# AIR_Control1_Main_080116.net
KiCad netlist of a schematic drawn in Altium Designer
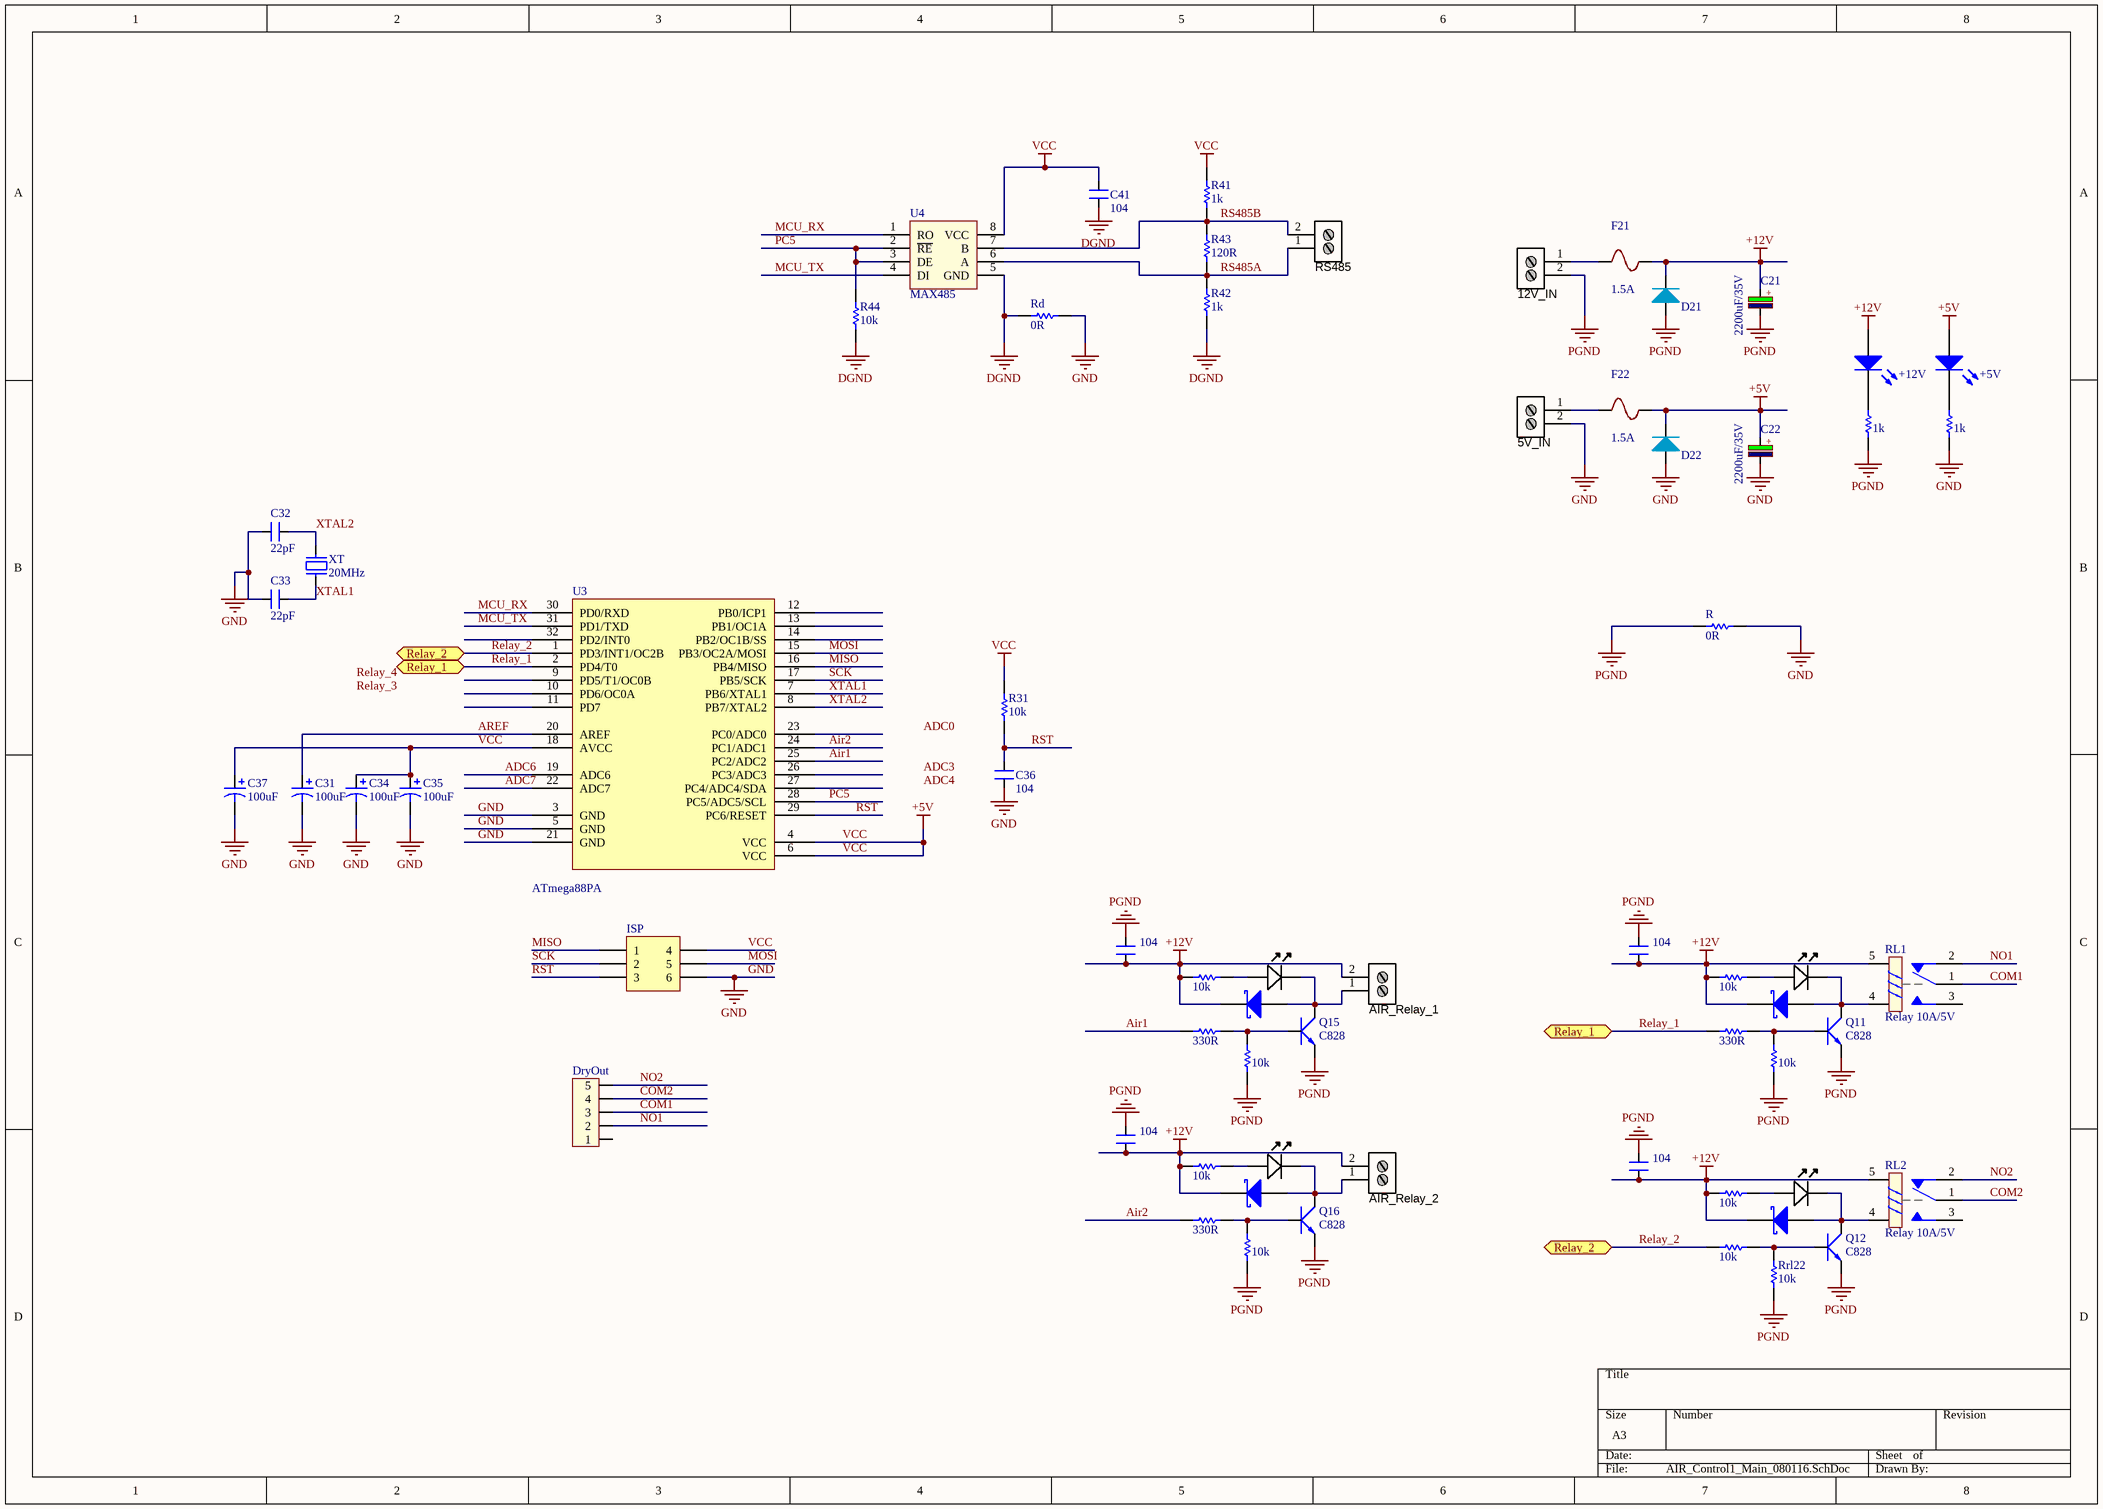
[diagram p0: AIR_Control1_Main_080116.SchDoc]

(export (version "E")
  (design (tool "Eeschema 10.0.6"))
  (components
    (comp (ref "+5V") (value "Led") (footprint "LED 5mm RED") (libsource (lib "Tuan") (part "Led")))
    (comp (ref "+12V") (value "Led") (footprint "LED 5mm RED") (libsource (lib "Tuan") (part "Led")))
    (comp (ref "5V_IN")
      (value "Stackable ScrewTerm")
      (footprint "2P_PCB_ScrewTerm_200mil")
      (description "Terminal Block Screw Type THT 2-Position 3.81mm pitch")
      (libsource (lib "") (part "2P_ScrewTerm_90S_3.81MM_1"))
    )
    (comp (ref "12V_IN")
      (value "Stackable ScrewTerm")
      (footprint "2P_PCB_ScrewTerm_200mil")
      (description "Terminal Block Screw Type THT 2-Position 3.81mm pitch")
      (libsource (lib "") (part "2P_ScrewTerm_90S_3.81MM_1"))
    )
    (comp (ref "AIR_Relay_1")
      (value "Stackable ScrewTerm")
      (footprint "2P_PCB_ScrewTerm_200mil")
      (description "Terminal Block Screw Type THT 2-Position 3.81mm pitch")
      (libsource (lib "PBL - Connectors") (part "2P_ScrewTerm_90S_3.81MM"))
    )
    (comp (ref "AIR_Relay_2")
      (value "Stackable ScrewTerm")
      (footprint "2P_PCB_ScrewTerm_200mil")
      (description "Terminal Block Screw Type THT 2-Position 3.81mm pitch")
      (libsource (lib "PBL - Connectors") (part "2P_ScrewTerm_90S_3.81MM"))
    )
    (comp (ref "C21")
      (value "2200uF/35V")
      (footprint "heromap:CP_1000uF_25V")
      (description "Cap 1000uF/16V - 220uF/50V")
      (libsource (lib "heromap") (part "CP4"))
    )
    (comp (ref "C22")
      (value "2200uF/35V")
      (footprint "heromap:CP_1000uF_25V")
      (description "Cap 1000uF/16V - 220uF/50V")
      (libsource (lib "heromap") (part "CP4"))
    )
    (comp (ref "C31")
      (value "100uF")
      (footprint "CAPC2012N_F")
      (fields (field (name "Comment") "Cap"))
      (libsource (lib "Tuan") (part "Cap"))
    )
    (comp (ref "C32")
      (value "22pF")
      (footprint "CAPC1608N")
      (fields (field (name "Comment") "CAP NP"))
      (libsource (lib "Tuan") (part "CAP NP"))
    )
    (comp (ref "C33")
      (value "22pF")
      (footprint "CAPC1608N")
      (fields (field (name "Comment") "CAP NP"))
      (libsource (lib "Tuan") (part "CAP NP"))
    )
    (comp (ref "C34")
      (value "100uF")
      (footprint "CAPC2012N_F")
      (fields (field (name "Comment") "Cap"))
      (libsource (lib "Tuan") (part "Cap"))
    )
    (comp (ref "C35")
      (value "100uF")
      (footprint "CAPC2012N_F")
      (fields (field (name "Comment") "Cap"))
      (libsource (lib "Tuan") (part "Cap"))
    )
    (comp (ref "C36")
      (value "104")
      (footprint "CAPC1608N")
      (fields (field (name "Comment") "CAP NP"))
      (libsource (lib "Tuan") (part "CAP NP"))
    )
    (comp (ref "C37")
      (value "100uF")
      (footprint "CAPC2012N_F")
      (fields (field (name "Comment") "Cap"))
      (libsource (lib "Tuan") (part "Cap"))
    )
    (comp (ref "C41")
      (value "104")
      (footprint "CAPC2012N_F")
      (fields (field (name "Comment") "100nF/104"))
      (libsource (lib "Tuan") (part "CAP NP"))
    )
    (comp (ref "Crl1")
      (value "104")
      (footprint "CAPC2012N_F")
      (fields (field (name "Comment") "CAP NP"))
      (libsource (lib "Tuan") (part "CAP NP"))
    )
    (comp (ref "Crl2")
      (value "104")
      (footprint "CAPC2012N_F")
      (fields (field (name "Comment") "CAP NP"))
      (libsource (lib "Tuan") (part "CAP NP"))
    )
    (comp (ref "Crl5")
      (value "104")
      (footprint "CAPC2012N_F")
      (fields (field (name "Comment") "CAP NP"))
      (libsource (lib "Tuan") (part "CAP NP"))
    )
    (comp (ref "Crl6")
      (value "104")
      (footprint "CAPC2012N_F")
      (fields (field (name "Comment") "CAP NP"))
      (libsource (lib "Tuan") (part "CAP NP"))
    )
    (comp (ref "D11") (value "Diode") (footprint "DO-214AC") (libsource (lib "") (part "Diode_1")))
    (comp (ref "D12") (value "Diode") (footprint "DO-214AC") (libsource (lib "") (part "Diode_1")))
    (comp (ref "D15") (value "Diode") (footprint "DO-214AC") (libsource (lib "") (part "Diode_1")))
    (comp (ref "D16") (value "Diode") (footprint "DO-214AC") (libsource (lib "") (part "Diode_1")))
    (comp (ref "D21") (value "Diode") (footprint "DO-214AC") (libsource (lib "Tuan") (part "Diode")))
    (comp (ref "D22") (value "Diode") (footprint "DO-214AC") (libsource (lib "Tuan") (part "Diode")))
    (comp (ref "DryOut")
      (value "JP5")
      (footprint "heromap:CON5")
      (description "Connector 5")
      (libsource (lib "heromap") (part "Con5"))
    )
    (comp (ref "E1")
      (value "Blue")
      (footprint "LED-0805-A")
      (description "LED 0805 SMD Blue 100mcd 470nm")
      (libsource (lib "PBL - Light Sources") (part "LED_SMD_Blue_0805_100mcd"))
    )
    (comp (ref "E2")
      (value "Blue")
      (footprint "LED-0805-A")
      (description "LED 0805 SMD Blue 100mcd 470nm")
      (libsource (lib "PBL - Light Sources") (part "LED_SMD_Blue_0805_100mcd"))
    )
    (comp (ref "E5")
      (value "Blue")
      (footprint "LED-0805-A")
      (description "LED 0805 SMD Blue 100mcd 470nm")
      (libsource (lib "PBL - Light Sources") (part "LED_SMD_Blue_0805_100mcd"))
    )
    (comp (ref "E6")
      (value "Blue")
      (footprint "LED-0805-A")
      (description "LED 0805 SMD Blue 100mcd 470nm")
      (libsource (lib "PBL - Light Sources") (part "LED_SMD_Blue_0805_100mcd"))
    )
    (comp (ref "F21") (value "1.5A") (footprint "FUSE_SR-5-BK") (libsource (lib "Tuan") (part "Fuse")))
    (comp (ref "F22") (value "1.5A") (footprint "FUSE_SR-5-BK") (libsource (lib "Tuan") (part "Fuse")))
    (comp (ref "ISP")
      (value "Header 3X2A")
      (footprint "HDR2X3_CEN")
      (description "Header, 3-Pin, Dual row")
      (fields (field (name "PUBLISHER") "Altium Limited"))
      (libsource (lib "Miscellaneous Connectors") (part "Header 3X2A"))
    )
    (comp (ref "Q11")
      (value "C828")
      (footprint "SOT23 TOP")
      (description "Transistor C828 C1815....")
      (libsource (lib "Tuan") (part "NPN"))
    )
    (comp (ref "Q12")
      (value "C828")
      (footprint "SOT23 TOP")
      (description "Transistor C828 C1815....")
      (libsource (lib "Tuan") (part "NPN"))
    )
    (comp (ref "Q15")
      (value "C828")
      (footprint "SOT23 TOP")
      (description "Transistor C828 C1815....")
      (libsource (lib "Tuan") (part "NPN"))
    )
    (comp (ref "Q16")
      (value "C828")
      (footprint "SOT23 TOP")
      (description "Transistor C828 C1815....")
      (libsource (lib "Tuan") (part "NPN"))
    )
    (comp (ref "R")
      (value "0R")
      (footprint "RESTH_AXIAL-0.4")
      (fields (field (name "Comment") "Res"))
      (libsource (lib "Tuan") (part "Res"))
    )
    (comp (ref "R21")
      (value "1k")
      (footprint "RESC2012N_F")
      (fields (field (name "Comment") "Res_0805_1k"))
      (libsource (lib "Tuan") (part "Res"))
    )
    (comp (ref "R22")
      (value "1k")
      (footprint "RESC2012N_F")
      (fields (field (name "Comment") "Res_0805_1k"))
      (libsource (lib "Tuan") (part "Res"))
    )
    (comp (ref "R31")
      (value "10k")
      (footprint "RESC1608N_ZERO")
      (fields (field (name "Comment") "Res"))
      (libsource (lib "Tuan") (part "Res"))
    )
    (comp (ref "R41")
      (value "1k")
      (footprint "RESC2012N_F")
      (description "Tro dan")
      (libsource (lib "GPS_Clock_v12") (part "Res"))
    )
    (comp (ref "R42")
      (value "1k")
      (footprint "RESC2012N_F")
      (description "Tro dan")
      (libsource (lib "GPS_Clock_v12") (part "Res"))
    )
    (comp (ref "R43")
      (value "120R")
      (footprint "RESC2012N_F")
      (description "Tro dan")
      (fields (field (name "Comment") "330R"))
      (libsource (lib "GPS_Clock_v12") (part "Res"))
    )
    (comp (ref "R44")
      (value "10k")
      (footprint "RESC2012N_F")
      (description "Tro dan")
      (fields (field (name "Comment") "330R"))
      (libsource (lib "GPS_Clock_v12") (part "Res"))
    )
    (comp (ref "Rd")
      (value "0R")
      (footprint "RESC2012N_F")
      (fields (field (name "Comment") "Res"))
      (libsource (lib "Tuan") (part "Res"))
    )
    (comp (ref "RL1")
      (value "Relay 10A/5V")
      (footprint "RL_5PIN")
      (description "Relay SPDT,10A - 12VDC 5 Pin")
      (libsource (lib "syhaunguyen") (part "Relay 1"))
    )
    (comp (ref "RL2")
      (value "Relay 10A/5V")
      (footprint "RL_5PIN")
      (description "Relay SPDT,10A - 12VDC 5 Pin")
      (libsource (lib "syhaunguyen") (part "Relay 1"))
    )
    (comp (ref "Rl52")
      (value "10k")
      (footprint "RESC1608N_ZERO")
      (fields (field (name "Comment") "Res"))
      (libsource (lib "Tuan") (part "Res"))
    )
    (comp (ref "Rrl11")
      (value "330R")
      (footprint "RESC1608N_ZERO")
      (fields (field (name "Comment") "Res"))
      (libsource (lib "Tuan") (part "Res"))
    )
    (comp (ref "Rrl12")
      (value "10k")
      (footprint "RESC1608N_ZERO")
      (fields (field (name "Comment") "Res"))
      (libsource (lib "Tuan") (part "Res"))
    )
    (comp (ref "Rrl13")
      (value "10k")
      (footprint "RESC1608N_ZERO")
      (fields (field (name "Comment") "Res"))
      (libsource (lib "Tuan") (part "Res"))
    )
    (comp (ref "Rrl21")
      (value "10k")
      (footprint "RESC1608N_ZERO")
      (fields (field (name "Comment") "Res"))
      (libsource (lib "Tuan") (part "Res"))
    )
    (comp (ref "Rrl22")
      (value "10k")
      (footprint "RESC1608N_ZERO")
      (fields (field (name "Comment") "Res"))
      (libsource (lib "Tuan") (part "Res"))
    )
    (comp (ref "Rrl23")
      (value "10k")
      (footprint "RESC1608N_ZERO")
      (fields (field (name "Comment") "Res"))
      (libsource (lib "Tuan") (part "Res"))
    )
    (comp (ref "Rrl51")
      (value "330R")
      (footprint "RESC1608N_ZERO")
      (fields (field (name "Comment") "Res"))
      (libsource (lib "Tuan") (part "Res"))
    )
    (comp (ref "Rrl53")
      (value "10k")
      (footprint "RESC1608N_ZERO")
      (fields (field (name "Comment") "Res"))
      (libsource (lib "Tuan") (part "Res"))
    )
    (comp (ref "Rrl61")
      (value "330R")
      (footprint "RESC1608N_ZERO")
      (fields (field (name "Comment") "Res"))
      (libsource (lib "Tuan") (part "Res"))
    )
    (comp (ref "Rrl62")
      (value "10k")
      (footprint "RESC1608N_ZERO")
      (fields (field (name "Comment") "Res"))
      (libsource (lib "Tuan") (part "Res"))
    )
    (comp (ref "Rrl63")
      (value "10k")
      (footprint "RESC1608N_ZERO")
      (fields (field (name "Comment") "Res"))
      (libsource (lib "Tuan") (part "Res"))
    )
    (comp (ref "RS485")
      (value "Stackable ScrewTerm")
      (footprint "2P_PCB1")
      (description "Terminal Block Screw Type THT 2-Position 3.81mm pitch")
      (libsource (lib "PBL - Connectors") (part "2P_ScrewTerm_90S_3.81MM"))
    )
    (comp (ref "U3")
      (value "ATmega88PA")
      (footprint "32PIN")
      (description "ATmega48/168/328")
      (libsource (lib "Tuan") (part "ATmega48/168/328"))
    )
    (comp (ref "U4")
      (value "MAX485")
      (footprint "SO-8")
      (description "RS232 - RS485 (Same sn75176)")
      (libsource (lib "heromap") (part "MAX485"))
    )
    (comp (ref "XT") (value "20MHz") (footprint "XT2") (libsource (lib "Tuan") (part "Crystal")))
  )
  (nets
    (net (code "1") (name "+5V") (class "Default")
      (node (ref "+5V") (pin "1") (pinfunction "A_1") (pintype "passive"))
      (node (ref "C22") (pin "1") (pinfunction "1_1") (pintype "passive"))
      (node (ref "C34") (pin "1") (pinfunction "1_1") (pintype "passive"))
      (node (ref "C35") (pin "1") (pinfunction "1_1") (pintype "passive"))
      (node (ref "C37") (pin "1") (pinfunction "1_1") (pintype "passive"))
      (node (ref "C41") (pin "2") (pinfunction "2_2") (pintype "passive"))
      (node (ref "D22") (pin "2") (pinfunction "K_2") (pintype "passive"))
      (node (ref "F22") (pin "2") (pinfunction "2_2") (pintype "passive"))
      (node (ref "ISP") (pin "4") (pinfunction "4_4") (pintype "passive"))
      (node (ref "R31") (pin "2") (pinfunction "2_2") (pintype "passive"))
      (node (ref "R41") (pin "2") (pinfunction "2_2") (pintype "passive"))
      (node (ref "U3") (pin "18") (pinfunction "AVCC_18") (pintype "passive"))
      (node (ref "U3") (pin "4") (pinfunction "VCC_4") (pintype "passive"))
      (node (ref "U3") (pin "6") (pinfunction "VCC_6") (pintype "passive"))
      (node (ref "U4") (pin "8") (pinfunction "VCC_8") (pintype "passive"))
    )
    (net (code "2") (name "+12V") (class "Default")
      (node (ref "+12V") (pin "1") (pinfunction "A_1") (pintype "passive"))
      (node (ref "AIR_Relay_1") (pin "2") (pinfunction "2_2") (pintype "passive"))
      (node (ref "AIR_Relay_2") (pin "2") (pinfunction "2_2") (pintype "passive"))
      (node (ref "C21") (pin "1") (pinfunction "1_1") (pintype "passive"))
      (node (ref "Crl1") (pin "1") (pinfunction "1_1") (pintype "passive"))
      (node (ref "Crl2") (pin "1") (pinfunction "1_1") (pintype "passive"))
      (node (ref "Crl5") (pin "1") (pinfunction "1_1") (pintype "passive"))
      (node (ref "Crl6") (pin "1") (pinfunction "1_1") (pintype "passive"))
      (node (ref "D11") (pin "2") (pinfunction "K_2") (pintype "passive"))
      (node (ref "D12") (pin "2") (pinfunction "K_2") (pintype "passive"))
      (node (ref "D15") (pin "2") (pinfunction "K_2") (pintype "passive"))
      (node (ref "D16") (pin "2") (pinfunction "K_2") (pintype "passive"))
      (node (ref "D21") (pin "2") (pinfunction "K_2") (pintype "passive"))
      (node (ref "F21") (pin "2") (pinfunction "2_2") (pintype "passive"))
      (node (ref "RL1") (pin "5") (pinfunction "5_5") (pintype "passive"))
      (node (ref "RL2") (pin "5") (pinfunction "5_5") (pintype "passive"))
      (node (ref "Rrl13") (pin "2") (pinfunction "2_2") (pintype "passive"))
      (node (ref "Rrl23") (pin "2") (pinfunction "2_2") (pintype "passive"))
      (node (ref "Rrl53") (pin "2") (pinfunction "2_2") (pintype "passive"))
      (node (ref "Rrl63") (pin "2") (pinfunction "2_2") (pintype "passive"))
    )
    (net (code "6") (name "/ADC6") (class "Default")
      (node (ref "U3") (pin "19") (pinfunction "ADC6_19") (pintype "passive"))
    )
    (net (code "7") (name "/ADC7") (class "Default")
      (node (ref "U3") (pin "22") (pinfunction "ADC7_22") (pintype "passive"))
    )
    (net (code "8") (name "/AREF") (class "Default")
      (node (ref "C31") (pin "1") (pinfunction "1_1") (pintype "passive"))
      (node (ref "U3") (pin "20") (pinfunction "AREF_20") (pintype "passive"))
    )
    (net (code "9") (name "/Air1") (class "Default")
      (node (ref "Rrl51") (pin "1") (pinfunction "1_1") (pintype "passive"))
      (node (ref "U3") (pin "25") (pinfunction "PC2/ADC2_25") (pintype "passive"))
    )
    (net (code "10") (name "/Air2") (class "Default")
      (node (ref "Rrl61") (pin "1") (pinfunction "1_1") (pintype "passive"))
      (node (ref "U3") (pin "24") (pinfunction "PC1/ADC1_24") (pintype "passive"))
    )
    (net (code "11") (name "/COM1") (class "Default")
      (node (ref "DryOut") (pin "3") (pinfunction "3_3") (pintype "passive"))
      (node (ref "RL1") (pin "1") (pinfunction "1_1") (pintype "passive"))
    )
    (net (code "12") (name "/COM2") (class "Default")
      (node (ref "DryOut") (pin "4") (pinfunction "4_4") (pintype "passive"))
      (node (ref "RL2") (pin "1") (pinfunction "1_1") (pintype "passive"))
    )
    (net (code "13") (name "/MCU_RX") (class "Default")
      (node (ref "U3") (pin "30") (pinfunction "PD0/RXD_30") (pintype "passive"))
      (node (ref "U4") (pin "1") (pinfunction "RO_1") (pintype "passive"))
    )
    (net (code "14") (name "/MCU_TX") (class "Default")
      (node (ref "U3") (pin "31") (pinfunction "PD1/TXD_31") (pintype "passive"))
      (node (ref "U4") (pin "4") (pinfunction "DI_4") (pintype "passive"))
    )
    (net (code "15") (name "/MISO") (class "Default")
      (node (ref "ISP") (pin "1") (pinfunction "1_1") (pintype "passive"))
      (node (ref "U3") (pin "16") (pinfunction "PB4/MISO_16") (pintype "passive"))
    )
    (net (code "16") (name "/MOSI") (class "Default")
      (node (ref "ISP") (pin "5") (pinfunction "5_5") (pintype "passive"))
      (node (ref "U3") (pin "15") (pinfunction "PB3/OC2A/MOSI_15") (pintype "passive"))
    )
    (net (code "17") (name "/NO1") (class "Default")
      (node (ref "DryOut") (pin "2") (pinfunction "2_2") (pintype "passive"))
      (node (ref "RL1") (pin "2") (pinfunction "2_2") (pintype "passive"))
    )
    (net (code "18") (name "/NO2") (class "Default")
      (node (ref "DryOut") (pin "5") (pinfunction "5_5") (pintype "passive"))
      (node (ref "RL2") (pin "2") (pinfunction "2_2") (pintype "passive"))
    )
    (net (code "19") (name "/PC5") (class "Default")
      (node (ref "R44") (pin "2") (pinfunction "2_2") (pintype "passive"))
      (node (ref "U3") (pin "28") (pinfunction "PC5/ADC5/SCL_28") (pintype "passive"))
      (node (ref "U4") (pin "2") (pinfunction "~{RE}_2") (pintype "passive"))
      (node (ref "U4") (pin "3") (pinfunction "DE_3") (pintype "passive"))
    )
    (net (code "20") (name "/RS485A") (class "Default")
      (node (ref "R42") (pin "2") (pinfunction "2_2") (pintype "passive"))
      (node (ref "R43") (pin "1") (pinfunction "1_1") (pintype "passive"))
      (node (ref "RS485") (pin "1") (pinfunction "1_1") (pintype "passive"))
      (node (ref "U4") (pin "6") (pinfunction "A_6") (pintype "passive"))
    )
    (net (code "21") (name "/RS485B") (class "Default")
      (node (ref "R41") (pin "1") (pinfunction "1_1") (pintype "passive"))
      (node (ref "R43") (pin "2") (pinfunction "2_2") (pintype "passive"))
      (node (ref "RS485") (pin "2") (pinfunction "2_2") (pintype "passive"))
      (node (ref "U4") (pin "7") (pinfunction "B_7") (pintype "passive"))
    )
    (net (code "22") (name "/RST") (class "Default")
      (node (ref "C36") (pin "2") (pinfunction "2_2") (pintype "passive"))
      (node (ref "ISP") (pin "3") (pinfunction "3_3") (pintype "passive"))
      (node (ref "R31") (pin "1") (pinfunction "1_1") (pintype "passive"))
      (node (ref "U3") (pin "29") (pinfunction "PC6/RESET_29") (pintype "passive"))
    )
    (net (code "23") (name "/Relay_1") (class "Default")
      (node (ref "Rrl11") (pin "1") (pinfunction "1_1") (pintype "passive"))
      (node (ref "U3") (pin "2") (pinfunction "PD4/T0_2") (pintype "passive"))
    )
    (net (code "24") (name "/Relay_2") (class "Default")
      (node (ref "Rrl21") (pin "1") (pinfunction "1_1") (pintype "passive"))
      (node (ref "U3") (pin "1") (pinfunction "PD3/INT1/OC2B_1") (pintype "passive"))
    )
    (net (code "27") (name "/SCK") (class "Default")
      (node (ref "ISP") (pin "2") (pinfunction "2_2") (pintype "passive"))
      (node (ref "U3") (pin "17") (pinfunction "PB5/SCK_17") (pintype "passive"))
    )
    (net (code "28") (name "/XTAL1") (class "Default")
      (node (ref "C33") (pin "1") (pinfunction "1_1") (pintype "passive"))
      (node (ref "U3") (pin "7") (pinfunction "PB6/XTAL1_7") (pintype "passive"))
      (node (ref "XT") (pin "1") (pinfunction "1_1") (pintype "passive"))
    )
    (net (code "29") (name "/XTAL2") (class "Default")
      (node (ref "C32") (pin "1") (pinfunction "1_1") (pintype "passive"))
      (node (ref "U3") (pin "8") (pinfunction "PB7/XTAL2_8") (pintype "passive"))
      (node (ref "XT") (pin "2") (pinfunction "2_2") (pintype "passive"))
    )
    (net (code "30") (name "DGND") (class "Default")
      (node (ref "C41") (pin "1") (pinfunction "1_1") (pintype "passive"))
      (node (ref "R42") (pin "1") (pinfunction "1_1") (pintype "passive"))
      (node (ref "R44") (pin "1") (pinfunction "1_1") (pintype "passive"))
      (node (ref "Rd") (pin "1") (pinfunction "1_1") (pintype "passive"))
      (node (ref "U4") (pin "5") (pinfunction "GND_5") (pintype "passive"))
    )
    (net (code "31") (name "GND") (class "Default")
      (node (ref "5V_IN") (pin "2") (pinfunction "2_2") (pintype "passive"))
      (node (ref "C22") (pin "2") (pinfunction "2_2") (pintype "passive"))
      (node (ref "C31") (pin "2") (pinfunction "2_2") (pintype "passive"))
      (node (ref "C32") (pin "2") (pinfunction "2_2") (pintype "passive"))
      (node (ref "C33") (pin "2") (pinfunction "2_2") (pintype "passive"))
      (node (ref "C34") (pin "2") (pinfunction "2_2") (pintype "passive"))
      (node (ref "C35") (pin "2") (pinfunction "2_2") (pintype "passive"))
      (node (ref "C36") (pin "1") (pinfunction "1_1") (pintype "passive"))
      (node (ref "C37") (pin "2") (pinfunction "2_2") (pintype "passive"))
      (node (ref "D22") (pin "1") (pinfunction "A_1") (pintype "passive"))
      (node (ref "ISP") (pin "6") (pinfunction "6_6") (pintype "passive"))
      (node (ref "R") (pin "2") (pinfunction "2_2") (pintype "passive"))
      (node (ref "R22") (pin "2") (pinfunction "2_2") (pintype "passive"))
      (node (ref "Rd") (pin "2") (pinfunction "2_2") (pintype "passive"))
      (node (ref "U3") (pin "21") (pinfunction "GND_21") (pintype "power_in"))
      (node (ref "U3") (pin "3") (pinfunction "GND_3") (pintype "power_in"))
      (node (ref "U3") (pin "5") (pinfunction "GND_5") (pintype "power_in"))
    )
    (net (code "32") (name "Net-(+5V-K)") (class "Default")
      (node (ref "+5V") (pin "2") (pinfunction "K_2") (pintype "passive"))
      (node (ref "R22") (pin "1") (pinfunction "1_1") (pintype "passive"))
    )
    (net (code "33") (name "Net-(+12V-K)") (class "Default")
      (node (ref "+12V") (pin "2") (pinfunction "K_2") (pintype "passive"))
      (node (ref "R21") (pin "1") (pinfunction "1_1") (pintype "passive"))
    )
    (net (code "34") (name "Net-(5V_IN-Pad1)") (class "Default")
      (node (ref "5V_IN") (pin "1") (pinfunction "1_1") (pintype "passive"))
      (node (ref "F22") (pin "1") (pinfunction "1_1") (pintype "passive"))
    )
    (net (code "35") (name "Net-(12V_IN-Pad1)") (class "Default")
      (node (ref "12V_IN") (pin "1") (pinfunction "1_1") (pintype "passive"))
      (node (ref "F21") (pin "1") (pinfunction "1_1") (pintype "passive"))
    )
    (net (code "36") (name "Net-(D11-A)") (class "Default")
      (node (ref "D11") (pin "1") (pinfunction "A_1") (pintype "passive"))
      (node (ref "E1") (pin "K") (pinfunction "K_K") (pintype "passive"))
      (node (ref "Q11") (pin "2") (pinfunction "C_2") (pintype "passive"))
      (node (ref "RL1") (pin "4") (pinfunction "4_4") (pintype "passive"))
    )
    (net (code "37") (name "Net-(D12-A)") (class "Default")
      (node (ref "D12") (pin "1") (pinfunction "A_1") (pintype "passive"))
      (node (ref "E2") (pin "K") (pinfunction "K_K") (pintype "passive"))
      (node (ref "Q12") (pin "2") (pinfunction "C_2") (pintype "passive"))
      (node (ref "RL2") (pin "4") (pinfunction "4_4") (pintype "passive"))
    )
    (net (code "38") (name "Net-(D15-A)") (class "Default")
      (node (ref "AIR_Relay_1") (pin "1") (pinfunction "1_1") (pintype "passive"))
      (node (ref "D15") (pin "1") (pinfunction "A_1") (pintype "passive"))
      (node (ref "E5") (pin "K") (pinfunction "K_K") (pintype "passive"))
      (node (ref "Q15") (pin "2") (pinfunction "C_2") (pintype "passive"))
    )
    (net (code "39") (name "Net-(D16-A)") (class "Default")
      (node (ref "AIR_Relay_2") (pin "1") (pinfunction "1_1") (pintype "passive"))
      (node (ref "D16") (pin "1") (pinfunction "A_1") (pintype "passive"))
      (node (ref "E6") (pin "K") (pinfunction "K_K") (pintype "passive"))
      (node (ref "Q16") (pin "2") (pinfunction "C_2") (pintype "passive"))
    )
    (net (code "40") (name "Net-(E1-PadA)") (class "Default")
      (node (ref "E1") (pin "A") (pinfunction "A_A") (pintype "passive"))
      (node (ref "Rrl13") (pin "1") (pinfunction "1_1") (pintype "passive"))
    )
    (net (code "41") (name "Net-(E2-PadA)") (class "Default")
      (node (ref "E2") (pin "A") (pinfunction "A_A") (pintype "passive"))
      (node (ref "Rrl23") (pin "1") (pinfunction "1_1") (pintype "passive"))
    )
    (net (code "42") (name "Net-(E5-PadA)") (class "Default")
      (node (ref "E5") (pin "A") (pinfunction "A_A") (pintype "passive"))
      (node (ref "Rrl53") (pin "1") (pinfunction "1_1") (pintype "passive"))
    )
    (net (code "43") (name "Net-(E6-PadA)") (class "Default")
      (node (ref "E6") (pin "A") (pinfunction "A_A") (pintype "passive"))
      (node (ref "Rrl63") (pin "1") (pinfunction "1_1") (pintype "passive"))
    )
    (net (code "44") (name "Net-(Q11-B)") (class "Default")
      (node (ref "Q11") (pin "1") (pinfunction "B_1") (pintype "passive"))
      (node (ref "Rrl11") (pin "2") (pinfunction "2_2") (pintype "passive"))
      (node (ref "Rrl12") (pin "2") (pinfunction "2_2") (pintype "passive"))
    )
    (net (code "45") (name "Net-(Q12-B)") (class "Default")
      (node (ref "Q12") (pin "1") (pinfunction "B_1") (pintype "passive"))
      (node (ref "Rrl21") (pin "2") (pinfunction "2_2") (pintype "passive"))
      (node (ref "Rrl22") (pin "2") (pinfunction "2_2") (pintype "passive"))
    )
    (net (code "46") (name "Net-(Q15-B)") (class "Default")
      (node (ref "Q15") (pin "1") (pinfunction "B_1") (pintype "passive"))
      (node (ref "Rl52") (pin "2") (pinfunction "2_2") (pintype "passive"))
      (node (ref "Rrl51") (pin "2") (pinfunction "2_2") (pintype "passive"))
    )
    (net (code "47") (name "Net-(Q16-B)") (class "Default")
      (node (ref "Q16") (pin "1") (pinfunction "B_1") (pintype "passive"))
      (node (ref "Rrl61") (pin "2") (pinfunction "2_2") (pintype "passive"))
      (node (ref "Rrl62") (pin "2") (pinfunction "2_2") (pintype "passive"))
    )
    (net (code "48") (name "PGND") (class "Default")
      (node (ref "12V_IN") (pin "2") (pinfunction "2_2") (pintype "passive"))
      (node (ref "C21") (pin "2") (pinfunction "2_2") (pintype "passive"))
      (node (ref "Crl1") (pin "2") (pinfunction "2_2") (pintype "passive"))
      (node (ref "Crl2") (pin "2") (pinfunction "2_2") (pintype "passive"))
      (node (ref "Crl5") (pin "2") (pinfunction "2_2") (pintype "passive"))
      (node (ref "Crl6") (pin "2") (pinfunction "2_2") (pintype "passive"))
      (node (ref "D21") (pin "1") (pinfunction "A_1") (pintype "passive"))
      (node (ref "Q11") (pin "3") (pinfunction "E_3") (pintype "passive"))
      (node (ref "Q12") (pin "3") (pinfunction "E_3") (pintype "passive"))
      (node (ref "Q15") (pin "3") (pinfunction "E_3") (pintype "passive"))
      (node (ref "Q16") (pin "3") (pinfunction "E_3") (pintype "passive"))
      (node (ref "R") (pin "1") (pinfunction "1_1") (pintype "passive"))
      (node (ref "R21") (pin "2") (pinfunction "2_2") (pintype "passive"))
      (node (ref "Rl52") (pin "1") (pinfunction "1_1") (pintype "passive"))
      (node (ref "Rrl12") (pin "1") (pinfunction "1_1") (pintype "passive"))
      (node (ref "Rrl22") (pin "1") (pinfunction "1_1") (pintype "passive"))
      (node (ref "Rrl62") (pin "1") (pinfunction "1_1") (pintype "passive"))
    )
    (net (code "49") (name "unconnected-(DryOut-Pad1)") (class "Default")
      (node (ref "DryOut") (pin "1") (pinfunction "1_1") (pintype "passive"))
    )
    (net (code "50") (name "unconnected-(RL1-Pad3)") (class "Default")
      (node (ref "RL1") (pin "3") (pinfunction "3_3") (pintype "passive"))
    )
    (net (code "51") (name "unconnected-(RL2-Pad3)") (class "Default")
      (node (ref "RL2") (pin "3") (pinfunction "3_3") (pintype "passive"))
    )
    (net (code "52") (name "unconnected-(U3-PB0{slash}ICP1-Pad12)") (class "Default")
      (node (ref "U3") (pin "12") (pinfunction "PB0/ICP1_12") (pintype "passive"))
    )
    (net (code "53") (name "unconnected-(U3-PB1{slash}OC1A-Pad13)") (class "Default")
      (node (ref "U3") (pin "13") (pinfunction "PB1/OC1A_13") (pintype "passive"))
    )
    (net (code "54") (name "unconnected-(U3-PB2{slash}OC1B{slash}SS-Pad14)") (class "Default")
      (node (ref "U3") (pin "14") (pinfunction "PB2/OC1B/SS_14") (pintype "passive"))
    )
    (net (code "55") (name "unconnected-(U3-PC0{slash}ADC0-Pad23)") (class "Default")
      (node (ref "U3") (pin "23") (pinfunction "PC0/ADC0_23") (pintype "passive"))
    )
    (net (code "56") (name "unconnected-(U3-PC3{slash}ADC3-Pad26)") (class "Default")
      (node (ref "U3") (pin "26") (pinfunction "PC3/ADC3_26") (pintype "passive"))
    )
    (net (code "57") (name "unconnected-(U3-PC4{slash}ADC4{slash}SDA-Pad27)") (class "Default")
      (node (ref "U3") (pin "27") (pinfunction "PC4/ADC4/SDA_27") (pintype "passive"))
    )
    (net (code "58") (name "unconnected-(U3-PD2{slash}INT0-Pad32)") (class "Default")
      (node (ref "U3") (pin "32") (pinfunction "PD2/INT0_32") (pintype "passive"))
    )
    (net (code "59") (name "unconnected-(U3-PD5{slash}T1{slash}OC0B-Pad9)") (class "Default")
      (node (ref "U3") (pin "9") (pinfunction "PD5/T1/OC0B_9") (pintype "passive"))
    )
    (net (code "60") (name "unconnected-(U3-PD6{slash}OC0A-Pad10)") (class "Default")
      (node (ref "U3") (pin "10") (pinfunction "PD6/OC0A_10") (pintype "passive"))
    )
    (net (code "61") (name "unconnected-(U3-PD7-Pad11)") (class "Default")
      (node (ref "U3") (pin "11") (pinfunction "PD7_11") (pintype "passive"))
    )
  )
)
